# Analog_Transmission.net
KiCad netlist of a schematic drawn in Altium Designer
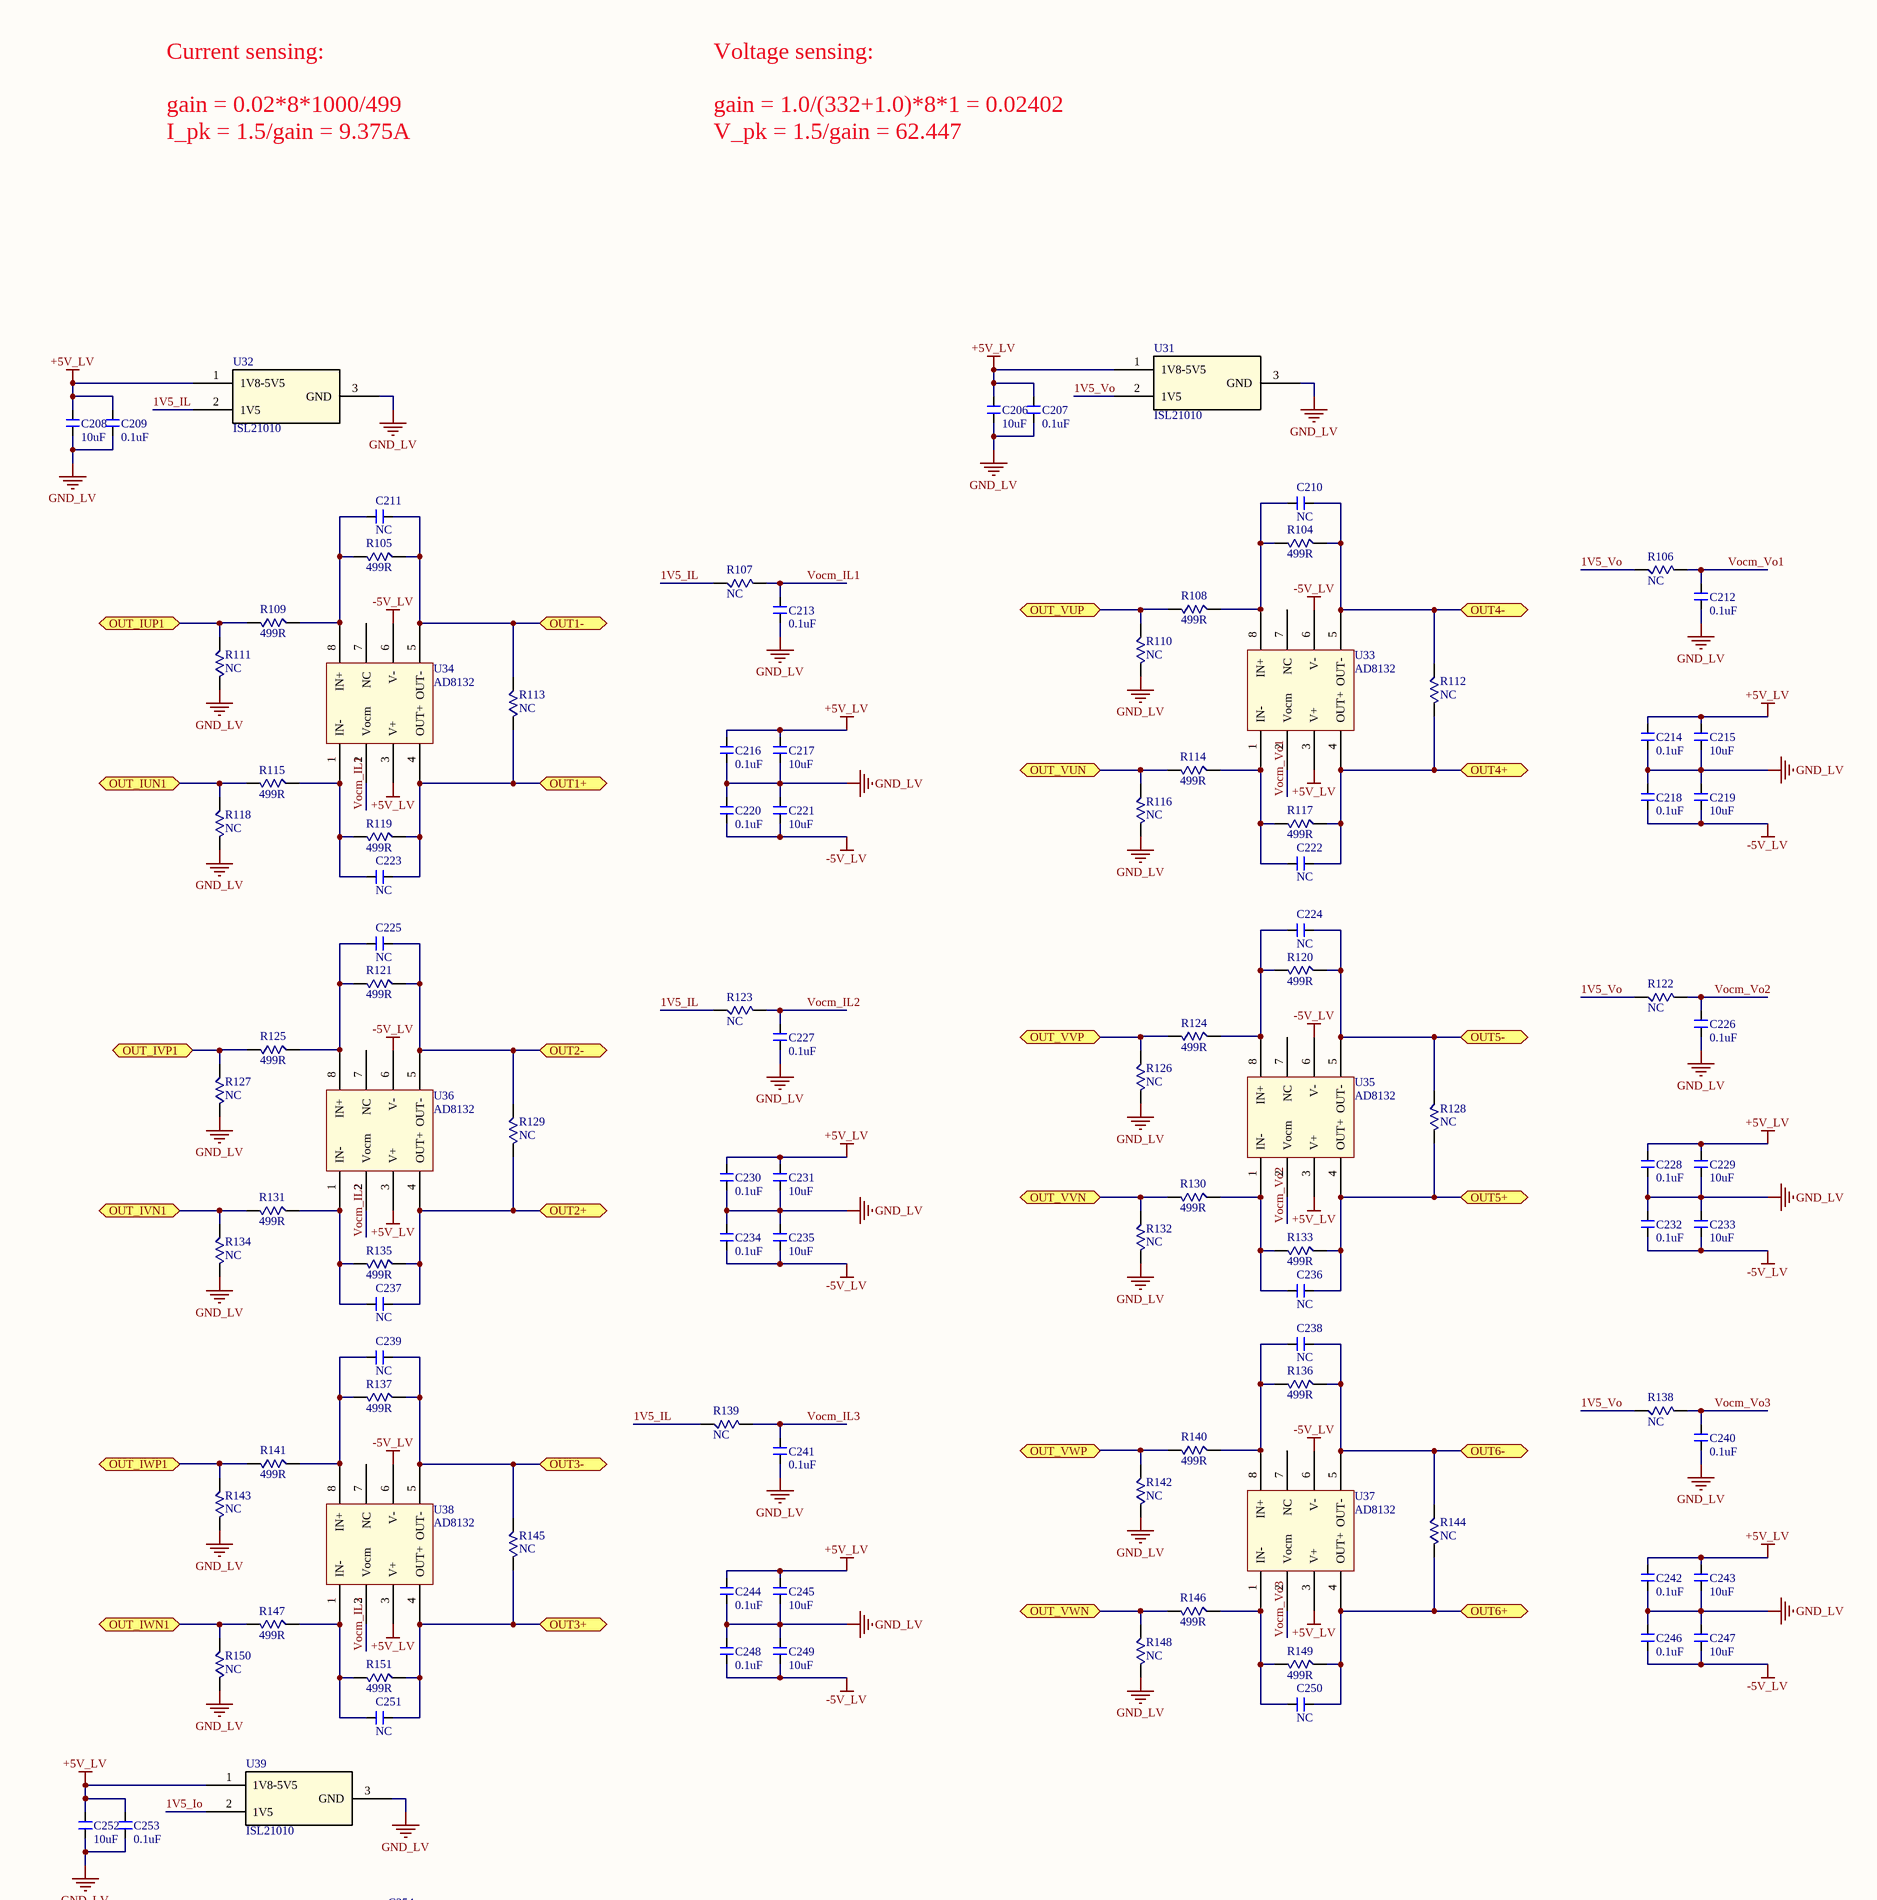
[diagram p0: Analog Transmission.SchDoc, top]
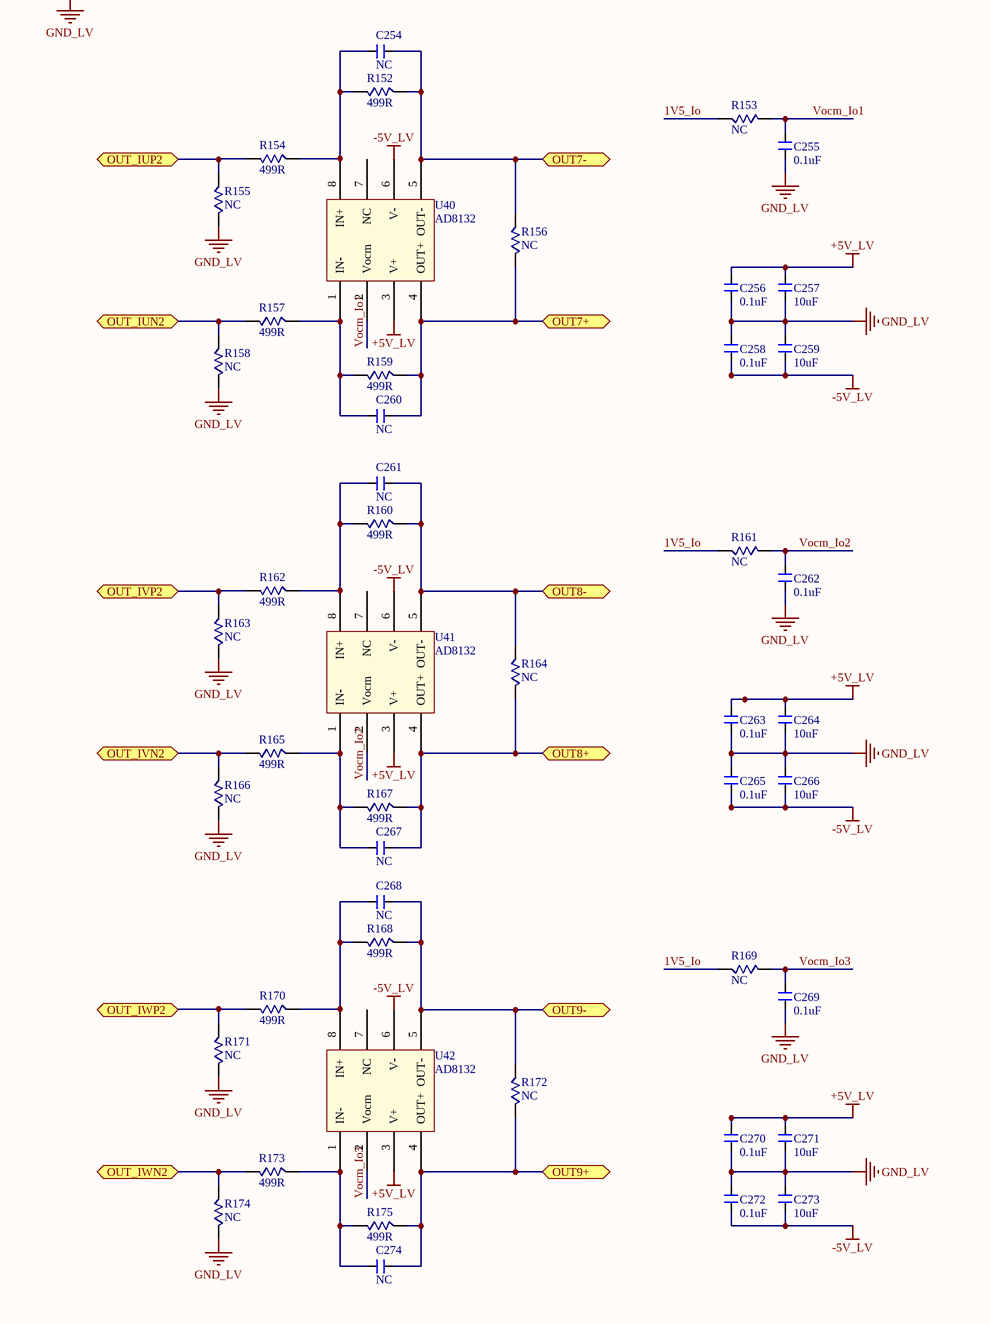
[diagram p1: Analog Transmission.SchDoc, bottom]

(export (version "E")
  (design (tool "Eeschema 10.0.6"))
  (components
    (comp (ref "C206")
      (value "10uF")
      (footprint "0603 (1608 Metric)")
      (description "CAP CER 10UF 35V X5R 0805")
      (fields (field (name "PART") "490-10515-1-ND") (field (name "Comment") "Cap 0603_new"))
      (libsource (lib "Library_Microgrid") (part "Cap 0603_new"))
    )
    (comp (ref "C207")
      (value "0.1uF")
      (footprint "0603 (1608 Metric)")
      (description "CAP CER 0.1UF 50V Y5V 0603")
      (fields (field (name "PART") "311-1343-6-ND") (field (name "Comment") "Cap 0603_new"))
      (libsource (lib "Library_Microgrid") (part "Cap 0603_new"))
    )
    (comp (ref "C208")
      (value "10uF")
      (footprint "0603 (1608 Metric)")
      (description "CAP CER 10UF 35V X5R 0805")
      (fields (field (name "PART") "490-10515-1-ND") (field (name "Comment") "Cap 0603_new"))
      (libsource (lib "Library_Microgrid") (part "Cap 0603_new"))
    )
    (comp (ref "C209")
      (value "0.1uF")
      (footprint "0603 (1608 Metric)")
      (description "CAP CER 0.1UF 50V Y5V 0603")
      (fields (field (name "PART") "311-1343-6-ND") (field (name "Comment") "Cap 0603_new"))
      (libsource (lib "Library_Microgrid") (part "Cap 0603_new"))
    )
    (comp (ref "C210")
      (value "NC")
      (footprint "0603 (1608 Metric)")
      (fields (field (name "Comment") "Cap 0603_new"))
      (libsource (lib "Library_Microgrid") (part "Cap 0603_new"))
    )
    (comp (ref "C211")
      (value "NC")
      (footprint "0603 (1608 Metric)")
      (fields (field (name "Comment") "Cap 0603_new"))
      (libsource (lib "Library_Microgrid") (part "Cap 0603_new"))
    )
    (comp (ref "C212")
      (value "0.1uF")
      (footprint "0603 (1608 Metric)")
      (description "CAP CER 0.1UF 50V Y5V 0603")
      (fields (field (name "PART") "311-1343-6-ND") (field (name "Comment") "Cap 0603_new"))
      (libsource (lib "Library_Microgrid") (part "Cap 0603_new"))
    )
    (comp (ref "C213")
      (value "0.1uF")
      (footprint "0603 (1608 Metric)")
      (description "CAP CER 0.1UF 50V Y5V 0603")
      (fields (field (name "PART") "311-1343-6-ND") (field (name "Comment") "Cap 0603_new"))
      (libsource (lib "Library_Microgrid") (part "Cap 0603_new"))
    )
    (comp (ref "C214")
      (value "0.1uF")
      (footprint "0603 (1608 Metric)")
      (description "CAP CER 0.1UF 50V Y5V 0603")
      (fields (field (name "PART") "311-1343-6-ND") (field (name "Comment") "Cap 0603_new"))
      (libsource (lib "Library_Microgrid") (part "Cap 0603_new"))
    )
    (comp (ref "C215")
      (value "10uF")
      (footprint "0603 (1608 Metric)")
      (description "CAP CER 10UF 35V X5R 0805")
      (fields (field (name "PART") "490-10515-1-ND") (field (name "Comment") "Cap 0603_new"))
      (libsource (lib "Library_Microgrid") (part "Cap 0603_new"))
    )
    (comp (ref "C216")
      (value "0.1uF")
      (footprint "0603 (1608 Metric)")
      (description "CAP CER 0.1UF 50V Y5V 0603")
      (fields (field (name "PART") "311-1343-6-ND") (field (name "Comment") "Cap 0603_new"))
      (libsource (lib "Library_Microgrid") (part "Cap 0603_new"))
    )
    (comp (ref "C217")
      (value "10uF")
      (footprint "0603 (1608 Metric)")
      (description "CAP CER 10UF 35V X5R 0805")
      (fields (field (name "PART") "490-10515-1-ND") (field (name "Comment") "Cap 0603_new"))
      (libsource (lib "Library_Microgrid") (part "Cap 0603_new"))
    )
    (comp (ref "C218")
      (value "0.1uF")
      (footprint "0603 (1608 Metric)")
      (description "CAP CER 0.1UF 50V Y5V 0603")
      (fields (field (name "PART") "311-1343-6-ND") (field (name "Comment") "Cap 0603_new"))
      (libsource (lib "Library_Microgrid") (part "Cap 0603_new"))
    )
    (comp (ref "C219")
      (value "10uF")
      (footprint "0603 (1608 Metric)")
      (description "CAP CER 10UF 35V X5R 0805")
      (fields (field (name "PART") "490-10515-1-ND") (field (name "Comment") "Cap 0603_new"))
      (libsource (lib "Library_Microgrid") (part "Cap 0603_new"))
    )
    (comp (ref "C220")
      (value "0.1uF")
      (footprint "0603 (1608 Metric)")
      (description "CAP CER 0.1UF 50V Y5V 0603")
      (fields (field (name "PART") "311-1343-6-ND") (field (name "Comment") "Cap 0603_new"))
      (libsource (lib "Library_Microgrid") (part "Cap 0603_new"))
    )
    (comp (ref "C221")
      (value "10uF")
      (footprint "0603 (1608 Metric)")
      (description "CAP CER 10UF 35V X5R 0805")
      (fields (field (name "PART") "490-10515-1-ND") (field (name "Comment") "Cap 0603_new"))
      (libsource (lib "Library_Microgrid") (part "Cap 0603_new"))
    )
    (comp (ref "C222")
      (value "NC")
      (footprint "0603 (1608 Metric)")
      (fields (field (name "Comment") "Cap 0603_new"))
      (libsource (lib "Library_Microgrid") (part "Cap 0603_new"))
    )
    (comp (ref "C223")
      (value "NC")
      (footprint "0603 (1608 Metric)")
      (fields (field (name "Comment") "Cap 0603_new"))
      (libsource (lib "Library_Microgrid") (part "Cap 0603_new"))
    )
    (comp (ref "C224")
      (value "NC")
      (footprint "0603 (1608 Metric)")
      (fields (field (name "Comment") "Cap 0603_new"))
      (libsource (lib "Library_Microgrid") (part "Cap 0603_new"))
    )
    (comp (ref "C225")
      (value "NC")
      (footprint "0603 (1608 Metric)")
      (fields (field (name "Comment") "Cap 0603_new"))
      (libsource (lib "Library_Microgrid") (part "Cap 0603_new"))
    )
    (comp (ref "C226")
      (value "0.1uF")
      (footprint "0603 (1608 Metric)")
      (description "CAP CER 0.1UF 50V Y5V 0603")
      (fields (field (name "PART") "311-1343-6-ND") (field (name "Comment") "Cap 0603_new"))
      (libsource (lib "Library_Microgrid") (part "Cap 0603_new"))
    )
    (comp (ref "C227")
      (value "0.1uF")
      (footprint "0603 (1608 Metric)")
      (description "CAP CER 0.1UF 50V Y5V 0603")
      (fields (field (name "PART") "311-1343-6-ND") (field (name "Comment") "Cap 0603_new"))
      (libsource (lib "Library_Microgrid") (part "Cap 0603_new"))
    )
    (comp (ref "C228")
      (value "0.1uF")
      (footprint "0603 (1608 Metric)")
      (description "CAP CER 0.1UF 50V Y5V 0603")
      (fields (field (name "PART") "311-1343-6-ND") (field (name "Comment") "Cap 0603_new"))
      (libsource (lib "Library_Microgrid") (part "Cap 0603_new"))
    )
    (comp (ref "C229")
      (value "10uF")
      (footprint "0603 (1608 Metric)")
      (description "CAP CER 10UF 35V X5R 0805")
      (fields (field (name "PART") "490-10515-1-ND") (field (name "Comment") "Cap 0603_new"))
      (libsource (lib "Library_Microgrid") (part "Cap 0603_new"))
    )
    (comp (ref "C230")
      (value "0.1uF")
      (footprint "0603 (1608 Metric)")
      (description "CAP CER 0.1UF 50V Y5V 0603")
      (fields (field (name "PART") "311-1343-6-ND") (field (name "Comment") "Cap 0603_new"))
      (libsource (lib "Library_Microgrid") (part "Cap 0603_new"))
    )
    (comp (ref "C231")
      (value "10uF")
      (footprint "0603 (1608 Metric)")
      (description "CAP CER 10UF 35V X5R 0805")
      (fields (field (name "PART") "490-10515-1-ND") (field (name "Comment") "Cap 0603_new"))
      (libsource (lib "Library_Microgrid") (part "Cap 0603_new"))
    )
    (comp (ref "C232")
      (value "0.1uF")
      (footprint "0603 (1608 Metric)")
      (description "CAP CER 0.1UF 50V Y5V 0603")
      (fields (field (name "PART") "311-1343-6-ND") (field (name "Comment") "Cap 0603_new"))
      (libsource (lib "Library_Microgrid") (part "Cap 0603_new"))
    )
    (comp (ref "C233")
      (value "10uF")
      (footprint "0603 (1608 Metric)")
      (description "CAP CER 10UF 35V X5R 0805")
      (fields (field (name "PART") "490-10515-1-ND") (field (name "Comment") "Cap 0603_new"))
      (libsource (lib "Library_Microgrid") (part "Cap 0603_new"))
    )
    (comp (ref "C234")
      (value "0.1uF")
      (footprint "0603 (1608 Metric)")
      (description "CAP CER 0.1UF 50V Y5V 0603")
      (fields (field (name "PART") "311-1343-6-ND") (field (name "Comment") "Cap 0603_new"))
      (libsource (lib "Library_Microgrid") (part "Cap 0603_new"))
    )
    (comp (ref "C235")
      (value "10uF")
      (footprint "0603 (1608 Metric)")
      (description "CAP CER 10UF 35V X5R 0805")
      (fields (field (name "PART") "490-10515-1-ND") (field (name "Comment") "Cap 0603_new"))
      (libsource (lib "Library_Microgrid") (part "Cap 0603_new"))
    )
    (comp (ref "C236")
      (value "NC")
      (footprint "0603 (1608 Metric)")
      (fields (field (name "Comment") "Cap 0603_new"))
      (libsource (lib "Library_Microgrid") (part "Cap 0603_new"))
    )
    (comp (ref "C237")
      (value "NC")
      (footprint "0603 (1608 Metric)")
      (fields (field (name "Comment") "Cap 0603_new"))
      (libsource (lib "Library_Microgrid") (part "Cap 0603_new"))
    )
    (comp (ref "C238")
      (value "NC")
      (footprint "0603 (1608 Metric)")
      (fields (field (name "Comment") "Cap 0603_new"))
      (libsource (lib "Library_Microgrid") (part "Cap 0603_new"))
    )
    (comp (ref "C239")
      (value "NC")
      (footprint "0603 (1608 Metric)")
      (fields (field (name "Comment") "Cap 0603_new"))
      (libsource (lib "Library_Microgrid") (part "Cap 0603_new"))
    )
    (comp (ref "C240")
      (value "0.1uF")
      (footprint "0603 (1608 Metric)")
      (description "CAP CER 0.1UF 50V Y5V 0603")
      (fields (field (name "PART") "311-1343-6-ND") (field (name "Comment") "Cap 0603_new"))
      (libsource (lib "Library_Microgrid") (part "Cap 0603_new"))
    )
    (comp (ref "C241")
      (value "0.1uF")
      (footprint "0603 (1608 Metric)")
      (description "CAP CER 0.1UF 50V Y5V 0603")
      (fields (field (name "PART") "311-1343-6-ND") (field (name "Comment") "Cap 0603_new"))
      (libsource (lib "Library_Microgrid") (part "Cap 0603_new"))
    )
    (comp (ref "C242")
      (value "0.1uF")
      (footprint "0603 (1608 Metric)")
      (description "CAP CER 0.1UF 50V Y5V 0603")
      (fields (field (name "PART") "311-1343-6-ND") (field (name "Comment") "Cap 0603_new"))
      (libsource (lib "Library_Microgrid") (part "Cap 0603_new"))
    )
    (comp (ref "C243")
      (value "10uF")
      (footprint "0603 (1608 Metric)")
      (description "CAP CER 10UF 35V X5R 0805")
      (fields (field (name "PART") "490-10515-1-ND") (field (name "Comment") "Cap 0603_new"))
      (libsource (lib "Library_Microgrid") (part "Cap 0603_new"))
    )
    (comp (ref "C244")
      (value "0.1uF")
      (footprint "0603 (1608 Metric)")
      (description "CAP CER 0.1UF 50V Y5V 0603")
      (fields (field (name "PART") "311-1343-6-ND") (field (name "Comment") "Cap 0603_new"))
      (libsource (lib "Library_Microgrid") (part "Cap 0603_new"))
    )
    (comp (ref "C245")
      (value "10uF")
      (footprint "0603 (1608 Metric)")
      (description "CAP CER 10UF 35V X5R 0805")
      (fields (field (name "PART") "490-10515-1-ND") (field (name "Comment") "Cap 0603_new"))
      (libsource (lib "Library_Microgrid") (part "Cap 0603_new"))
    )
    (comp (ref "C246")
      (value "0.1uF")
      (footprint "0603 (1608 Metric)")
      (description "CAP CER 0.1UF 50V Y5V 0603")
      (fields (field (name "PART") "311-1343-6-ND") (field (name "Comment") "Cap 0603_new"))
      (libsource (lib "Library_Microgrid") (part "Cap 0603_new"))
    )
    (comp (ref "C247")
      (value "10uF")
      (footprint "0603 (1608 Metric)")
      (description "CAP CER 10UF 35V X5R 0805")
      (fields (field (name "PART") "490-10515-1-ND") (field (name "Comment") "Cap 0603_new"))
      (libsource (lib "Library_Microgrid") (part "Cap 0603_new"))
    )
    (comp (ref "C248")
      (value "0.1uF")
      (footprint "0603 (1608 Metric)")
      (description "CAP CER 0.1UF 50V Y5V 0603")
      (fields (field (name "PART") "311-1343-6-ND") (field (name "Comment") "Cap 0603_new"))
      (libsource (lib "Library_Microgrid") (part "Cap 0603_new"))
    )
    (comp (ref "C249")
      (value "10uF")
      (footprint "0603 (1608 Metric)")
      (description "CAP CER 10UF 35V X5R 0805")
      (fields (field (name "PART") "490-10515-1-ND") (field (name "Comment") "Cap 0603_new"))
      (libsource (lib "Library_Microgrid") (part "Cap 0603_new"))
    )
    (comp (ref "C250")
      (value "NC")
      (footprint "0603 (1608 Metric)")
      (fields (field (name "Comment") "Cap 0603_new"))
      (libsource (lib "Library_Microgrid") (part "Cap 0603_new"))
    )
    (comp (ref "C251")
      (value "NC")
      (footprint "0603 (1608 Metric)")
      (fields (field (name "Comment") "Cap 0603_new"))
      (libsource (lib "Library_Microgrid") (part "Cap 0603_new"))
    )
    (comp (ref "C252")
      (value "10uF")
      (footprint "0603 (1608 Metric)")
      (description "CAP CER 10UF 35V X5R 0805")
      (fields (field (name "PART") "490-10515-1-ND") (field (name "Comment") "Cap 0603_new"))
      (libsource (lib "Library_Microgrid") (part "Cap 0603_new"))
    )
    (comp (ref "C253")
      (value "0.1uF")
      (footprint "0603 (1608 Metric)")
      (description "CAP CER 0.1UF 50V Y5V 0603")
      (fields (field (name "PART") "311-1343-6-ND") (field (name "Comment") "Cap 0603_new"))
      (libsource (lib "Library_Microgrid") (part "Cap 0603_new"))
    )
    (comp (ref "C254")
      (value "NC")
      (footprint "0603 (1608 Metric)")
      (fields (field (name "Comment") "Cap 0603_new"))
      (libsource (lib "Library_Microgrid") (part "Cap 0603_new"))
    )
    (comp (ref "C255")
      (value "0.1uF")
      (footprint "0603 (1608 Metric)")
      (description "CAP CER 0.1UF 50V Y5V 0603")
      (fields (field (name "PART") "311-1343-6-ND") (field (name "Comment") "Cap 0603_new"))
      (libsource (lib "Library_Microgrid") (part "Cap 0603_new"))
    )
    (comp (ref "C256")
      (value "0.1uF")
      (footprint "0603 (1608 Metric)")
      (description "CAP CER 0.1UF 50V Y5V 0603")
      (fields (field (name "PART") "311-1343-6-ND") (field (name "Comment") "Cap 0603_new"))
      (libsource (lib "Library_Microgrid") (part "Cap 0603_new"))
    )
    (comp (ref "C257")
      (value "10uF")
      (footprint "0603 (1608 Metric)")
      (description "CAP CER 10UF 35V X5R 0805")
      (fields (field (name "PART") "490-10515-1-ND") (field (name "Comment") "Cap 0603_new"))
      (libsource (lib "Library_Microgrid") (part "Cap 0603_new"))
    )
    (comp (ref "C258")
      (value "0.1uF")
      (footprint "0603 (1608 Metric)")
      (description "CAP CER 0.1UF 50V Y5V 0603")
      (fields (field (name "PART") "311-1343-6-ND") (field (name "Comment") "Cap 0603_new"))
      (libsource (lib "Library_Microgrid") (part "Cap 0603_new"))
    )
    (comp (ref "C259")
      (value "10uF")
      (footprint "0603 (1608 Metric)")
      (description "CAP CER 10UF 35V X5R 0805")
      (fields (field (name "PART") "490-10515-1-ND") (field (name "Comment") "Cap 0603_new"))
      (libsource (lib "Library_Microgrid") (part "Cap 0603_new"))
    )
    (comp (ref "C260")
      (value "NC")
      (footprint "0603 (1608 Metric)")
      (fields (field (name "Comment") "Cap 0603_new"))
      (libsource (lib "Library_Microgrid") (part "Cap 0603_new"))
    )
    (comp (ref "C261")
      (value "NC")
      (footprint "0603 (1608 Metric)")
      (fields (field (name "Comment") "Cap 0603_new"))
      (libsource (lib "Library_Microgrid") (part "Cap 0603_new"))
    )
    (comp (ref "C262")
      (value "0.1uF")
      (footprint "0603 (1608 Metric)")
      (description "CAP CER 0.1UF 50V Y5V 0603")
      (fields (field (name "PART") "311-1343-6-ND") (field (name "Comment") "Cap 0603_new"))
      (libsource (lib "Library_Microgrid") (part "Cap 0603_new"))
    )
    (comp (ref "C263")
      (value "0.1uF")
      (footprint "0603 (1608 Metric)")
      (description "CAP CER 0.1UF 50V Y5V 0603")
      (fields (field (name "PART") "311-1343-6-ND") (field (name "Comment") "Cap 0603_new"))
      (libsource (lib "Library_Microgrid") (part "Cap 0603_new"))
    )
    (comp (ref "C264")
      (value "10uF")
      (footprint "0603 (1608 Metric)")
      (description "CAP CER 10UF 35V X5R 0805")
      (fields (field (name "PART") "490-10515-1-ND") (field (name "Comment") "Cap 0603_new"))
      (libsource (lib "Library_Microgrid") (part "Cap 0603_new"))
    )
    (comp (ref "C265")
      (value "0.1uF")
      (footprint "0603 (1608 Metric)")
      (description "CAP CER 0.1UF 50V Y5V 0603")
      (fields (field (name "PART") "311-1343-6-ND") (field (name "Comment") "Cap 0603_new"))
      (libsource (lib "Library_Microgrid") (part "Cap 0603_new"))
    )
    (comp (ref "C266")
      (value "10uF")
      (footprint "0603 (1608 Metric)")
      (description "CAP CER 10UF 35V X5R 0805")
      (fields (field (name "PART") "490-10515-1-ND") (field (name "Comment") "Cap 0603_new"))
      (libsource (lib "Library_Microgrid") (part "Cap 0603_new"))
    )
    (comp (ref "C267")
      (value "NC")
      (footprint "0603 (1608 Metric)")
      (fields (field (name "Comment") "Cap 0603_new"))
      (libsource (lib "Library_Microgrid") (part "Cap 0603_new"))
    )
    (comp (ref "C268")
      (value "NC")
      (footprint "0603 (1608 Metric)")
      (fields (field (name "Comment") "Cap 0603_new"))
      (libsource (lib "Library_Microgrid") (part "Cap 0603_new"))
    )
    (comp (ref "C269")
      (value "0.1uF")
      (footprint "0603 (1608 Metric)")
      (description "CAP CER 0.1UF 50V Y5V 0603")
      (fields (field (name "PART") "311-1343-6-ND") (field (name "Comment") "Cap 0603_new"))
      (libsource (lib "Library_Microgrid") (part "Cap 0603_new"))
    )
    (comp (ref "C270")
      (value "0.1uF")
      (footprint "0603 (1608 Metric)")
      (description "CAP CER 0.1UF 50V Y5V 0603")
      (fields (field (name "PART") "311-1343-6-ND") (field (name "Comment") "Cap 0603_new"))
      (libsource (lib "Library_Microgrid") (part "Cap 0603_new"))
    )
    (comp (ref "C271")
      (value "10uF")
      (footprint "0603 (1608 Metric)")
      (description "CAP CER 10UF 35V X5R 0805")
      (fields (field (name "PART") "490-10515-1-ND") (field (name "Comment") "Cap 0603_new"))
      (libsource (lib "Library_Microgrid") (part "Cap 0603_new"))
    )
    (comp (ref "C272")
      (value "0.1uF")
      (footprint "0603 (1608 Metric)")
      (description "CAP CER 0.1UF 50V Y5V 0603")
      (fields (field (name "PART") "311-1343-6-ND") (field (name "Comment") "Cap 0603_new"))
      (libsource (lib "Library_Microgrid") (part "Cap 0603_new"))
    )
    (comp (ref "C273")
      (value "10uF")
      (footprint "0603 (1608 Metric)")
      (description "CAP CER 10UF 35V X5R 0805")
      (fields (field (name "PART") "490-10515-1-ND") (field (name "Comment") "Cap 0603_new"))
      (libsource (lib "Library_Microgrid") (part "Cap 0603_new"))
    )
    (comp (ref "C274")
      (value "NC")
      (footprint "0603 (1608 Metric)")
      (fields (field (name "Comment") "Cap 0603_new"))
      (libsource (lib "Library_Microgrid") (part "Cap 0603_new"))
    )
    (comp (ref "R104")
      (value "499R")
      (footprint "0603 (1608 Metric)")
      (description "RES SMD 499 OHM 0.1% 1/10W 0603")
      (fields (field (name "PART") "RG16P499BCT-ND") (field (name "Comment") "Resistor 0603"))
      (libsource (lib "Library_Microgrid") (part "Resistor 0603"))
    )
    (comp (ref "R105")
      (value "499R")
      (footprint "0603 (1608 Metric)")
      (description "RES SMD 499 OHM 0.1% 1/10W 0603")
      (fields (field (name "PART") "RG16P499BCT-ND") (field (name "Comment") "Resistor 0603"))
      (libsource (lib "Library_Microgrid") (part "Resistor 0603"))
    )
    (comp (ref "R106")
      (value "NC")
      (footprint "0603 (1608 Metric)")
      (fields (field (name "Comment") "Resistor 0603"))
      (libsource (lib "Library_Microgrid") (part "Resistor 0603"))
    )
    (comp (ref "R107")
      (value "NC")
      (footprint "0603 (1608 Metric)")
      (fields (field (name "Comment") "Resistor 0603"))
      (libsource (lib "Library_Microgrid") (part "Resistor 0603"))
    )
    (comp (ref "R108")
      (value "499R")
      (footprint "0603 (1608 Metric)")
      (description "RES SMD 499 OHM 0.1% 1/10W 0603")
      (fields (field (name "PART") "RG16P499BCT-ND") (field (name "Comment") "Resistor 0603"))
      (libsource (lib "Library_Microgrid") (part "Resistor 0603"))
    )
    (comp (ref "R109")
      (value "499R")
      (footprint "0603 (1608 Metric)")
      (description "RES SMD 499 OHM 0.1% 1/10W 0603")
      (fields (field (name "PART") "RG16P499BCT-ND") (field (name "Comment") "Resistor 0603"))
      (libsource (lib "Library_Microgrid") (part "Resistor 0603"))
    )
    (comp (ref "R110")
      (value "NC")
      (footprint "0603 (1608 Metric)")
      (fields (field (name "Comment") "Resistor 0603"))
      (libsource (lib "Library_Microgrid") (part "Resistor 0603"))
    )
    (comp (ref "R111")
      (value "NC")
      (footprint "0603 (1608 Metric)")
      (fields (field (name "Comment") "Resistor 0603"))
      (libsource (lib "Library_Microgrid") (part "Resistor 0603"))
    )
    (comp (ref "R112")
      (value "NC")
      (footprint "0603 (1608 Metric)")
      (fields (field (name "Comment") "Resistor 0603"))
      (libsource (lib "Library_Microgrid") (part "Resistor 0603"))
    )
    (comp (ref "R113")
      (value "NC")
      (footprint "0603 (1608 Metric)")
      (fields (field (name "Comment") "Resistor 0603"))
      (libsource (lib "Library_Microgrid") (part "Resistor 0603"))
    )
    (comp (ref "R114")
      (value "499R")
      (footprint "0603 (1608 Metric)")
      (description "RES SMD 499 OHM 0.1% 1/10W 0603")
      (fields (field (name "PART") "RG16P499BCT-ND") (field (name "Comment") "Resistor 0603"))
      (libsource (lib "Library_Microgrid") (part "Resistor 0603"))
    )
    (comp (ref "R115")
      (value "499R")
      (footprint "0603 (1608 Metric)")
      (description "RES SMD 499 OHM 0.1% 1/10W 0603")
      (fields (field (name "PART") "RG16P499BCT-ND") (field (name "Comment") "Resistor 0603"))
      (libsource (lib "Library_Microgrid") (part "Resistor 0603"))
    )
    (comp (ref "R116")
      (value "NC")
      (footprint "0603 (1608 Metric)")
      (fields (field (name "Comment") "Resistor 0603"))
      (libsource (lib "Library_Microgrid") (part "Resistor 0603"))
    )
    (comp (ref "R117")
      (value "499R")
      (footprint "0603 (1608 Metric)")
      (description "RES SMD 499 OHM 0.1% 1/10W 0603")
      (fields (field (name "PART") "RG16P499BCT-ND") (field (name "Comment") "Resistor 0603"))
      (libsource (lib "Library_Microgrid") (part "Resistor 0603"))
    )
    (comp (ref "R118")
      (value "NC")
      (footprint "0603 (1608 Metric)")
      (fields (field (name "Comment") "Resistor 0603"))
      (libsource (lib "Library_Microgrid") (part "Resistor 0603"))
    )
    (comp (ref "R119")
      (value "499R")
      (footprint "0603 (1608 Metric)")
      (description "RES SMD 499 OHM 0.1% 1/10W 0603")
      (fields (field (name "PART") "RG16P499BCT-ND") (field (name "Comment") "Resistor 0603"))
      (libsource (lib "Library_Microgrid") (part "Resistor 0603"))
    )
    (comp (ref "R120")
      (value "499R")
      (footprint "0603 (1608 Metric)")
      (description "RES SMD 499 OHM 0.1% 1/10W 0603")
      (fields (field (name "PART") "RG16P499BCT-ND") (field (name "Comment") "Resistor 0603"))
      (libsource (lib "Library_Microgrid") (part "Resistor 0603"))
    )
    (comp (ref "R121")
      (value "499R")
      (footprint "0603 (1608 Metric)")
      (description "RES SMD 499 OHM 0.1% 1/10W 0603")
      (fields (field (name "PART") "RG16P499BCT-ND") (field (name "Comment") "Resistor 0603"))
      (libsource (lib "Library_Microgrid") (part "Resistor 0603"))
    )
    (comp (ref "R122")
      (value "NC")
      (footprint "0603 (1608 Metric)")
      (fields (field (name "Comment") "Resistor 0603"))
      (libsource (lib "Library_Microgrid") (part "Resistor 0603"))
    )
    (comp (ref "R123")
      (value "NC")
      (footprint "0603 (1608 Metric)")
      (fields (field (name "Comment") "Resistor 0603"))
      (libsource (lib "Library_Microgrid") (part "Resistor 0603"))
    )
    (comp (ref "R124")
      (value "499R")
      (footprint "0603 (1608 Metric)")
      (description "RES SMD 499 OHM 0.1% 1/10W 0603")
      (fields (field (name "PART") "RG16P499BCT-ND") (field (name "Comment") "Resistor 0603"))
      (libsource (lib "Library_Microgrid") (part "Resistor 0603"))
    )
    (comp (ref "R125")
      (value "499R")
      (footprint "0603 (1608 Metric)")
      (description "RES SMD 499 OHM 0.1% 1/10W 0603")
      (fields (field (name "PART") "RG16P499BCT-ND") (field (name "Comment") "Resistor 0603"))
      (libsource (lib "Library_Microgrid") (part "Resistor 0603"))
    )
    (comp (ref "R126")
      (value "NC")
      (footprint "0603 (1608 Metric)")
      (fields (field (name "Comment") "Resistor 0603"))
      (libsource (lib "Library_Microgrid") (part "Resistor 0603"))
    )
    (comp (ref "R127")
      (value "NC")
      (footprint "0603 (1608 Metric)")
      (fields (field (name "Comment") "Resistor 0603"))
      (libsource (lib "Library_Microgrid") (part "Resistor 0603"))
    )
    (comp (ref "R128")
      (value "NC")
      (footprint "0603 (1608 Metric)")
      (fields (field (name "Comment") "Resistor 0603"))
      (libsource (lib "Library_Microgrid") (part "Resistor 0603"))
    )
    (comp (ref "R129")
      (value "NC")
      (footprint "0603 (1608 Metric)")
      (fields (field (name "Comment") "Resistor 0603"))
      (libsource (lib "Library_Microgrid") (part "Resistor 0603"))
    )
    (comp (ref "R130")
      (value "499R")
      (footprint "0603 (1608 Metric)")
      (description "RES SMD 499 OHM 0.1% 1/10W 0603")
      (fields (field (name "PART") "RG16P499BCT-ND") (field (name "Comment") "Resistor 0603"))
      (libsource (lib "Library_Microgrid") (part "Resistor 0603"))
    )
    (comp (ref "R131")
      (value "499R")
      (footprint "0603 (1608 Metric)")
      (description "RES SMD 499 OHM 0.1% 1/10W 0603")
      (fields (field (name "PART") "RG16P499BCT-ND") (field (name "Comment") "Resistor 0603"))
      (libsource (lib "Library_Microgrid") (part "Resistor 0603"))
    )
    (comp (ref "R132")
      (value "NC")
      (footprint "0603 (1608 Metric)")
      (fields (field (name "Comment") "Resistor 0603"))
      (libsource (lib "Library_Microgrid") (part "Resistor 0603"))
    )
    (comp (ref "R133")
      (value "499R")
      (footprint "0603 (1608 Metric)")
      (description "RES SMD 499 OHM 0.1% 1/10W 0603")
      (fields (field (name "PART") "RG16P499BCT-ND") (field (name "Comment") "Resistor 0603"))
      (libsource (lib "Library_Microgrid") (part "Resistor 0603"))
    )
    (comp (ref "R134")
      (value "NC")
      (footprint "0603 (1608 Metric)")
      (fields (field (name "Comment") "Resistor 0603"))
      (libsource (lib "Library_Microgrid") (part "Resistor 0603"))
    )
    (comp (ref "R135")
      (value "499R")
      (footprint "0603 (1608 Metric)")
      (description "RES SMD 499 OHM 0.1% 1/10W 0603")
      (fields (field (name "PART") "RG16P499BCT-ND") (field (name "Comment") "Resistor 0603"))
      (libsource (lib "Library_Microgrid") (part "Resistor 0603"))
    )
    (comp (ref "R136")
      (value "499R")
      (footprint "0603 (1608 Metric)")
      (description "RES SMD 499 OHM 0.1% 1/10W 0603")
      (fields (field (name "PART") "RG16P499BCT-ND") (field (name "Comment") "Resistor 0603"))
      (libsource (lib "Library_Microgrid") (part "Resistor 0603"))
    )
    (comp (ref "R137")
      (value "499R")
      (footprint "0603 (1608 Metric)")
      (description "RES SMD 499 OHM 0.1% 1/10W 0603")
      (fields (field (name "PART") "RG16P499BCT-ND") (field (name "Comment") "Resistor 0603"))
      (libsource (lib "Library_Microgrid") (part "Resistor 0603"))
    )
    (comp (ref "R138")
      (value "NC")
      (footprint "0603 (1608 Metric)")
      (fields (field (name "Comment") "Resistor 0603"))
      (libsource (lib "Library_Microgrid") (part "Resistor 0603"))
    )
    (comp (ref "R139")
      (value "NC")
      (footprint "0603 (1608 Metric)")
      (fields (field (name "Comment") "Resistor 0603"))
      (libsource (lib "Library_Microgrid") (part "Resistor 0603"))
    )
    (comp (ref "R140")
      (value "499R")
      (footprint "0603 (1608 Metric)")
      (description "RES SMD 499 OHM 0.1% 1/10W 0603")
      (fields (field (name "PART") "RG16P499BCT-ND") (field (name "Comment") "Resistor 0603"))
      (libsource (lib "Library_Microgrid") (part "Resistor 0603"))
    )
    (comp (ref "R141")
      (value "499R")
      (footprint "0603 (1608 Metric)")
      (description "RES SMD 499 OHM 0.1% 1/10W 0603")
      (fields (field (name "PART") "RG16P499BCT-ND") (field (name "Comment") "Resistor 0603"))
      (libsource (lib "Library_Microgrid") (part "Resistor 0603"))
    )
    (comp (ref "R142")
      (value "NC")
      (footprint "0603 (1608 Metric)")
      (fields (field (name "Comment") "Resistor 0603"))
      (libsource (lib "Library_Microgrid") (part "Resistor 0603"))
    )
    (comp (ref "R143")
      (value "NC")
      (footprint "0603 (1608 Metric)")
      (fields (field (name "Comment") "Resistor 0603"))
      (libsource (lib "Library_Microgrid") (part "Resistor 0603"))
    )
    (comp (ref "R144")
      (value "NC")
      (footprint "0603 (1608 Metric)")
      (fields (field (name "Comment") "Resistor 0603"))
      (libsource (lib "Library_Microgrid") (part "Resistor 0603"))
    )
    (comp (ref "R145")
      (value "NC")
      (footprint "0603 (1608 Metric)")
      (fields (field (name "Comment") "Resistor 0603"))
      (libsource (lib "Library_Microgrid") (part "Resistor 0603"))
    )
    (comp (ref "R146")
      (value "499R")
      (footprint "0603 (1608 Metric)")
      (description "RES SMD 499 OHM 0.1% 1/10W 0603")
      (fields (field (name "PART") "RG16P499BCT-ND") (field (name "Comment") "Resistor 0603"))
      (libsource (lib "Library_Microgrid") (part "Resistor 0603"))
    )
    (comp (ref "R147")
      (value "499R")
      (footprint "0603 (1608 Metric)")
      (description "RES SMD 499 OHM 0.1% 1/10W 0603")
      (fields (field (name "PART") "RG16P499BCT-ND") (field (name "Comment") "Resistor 0603"))
      (libsource (lib "Library_Microgrid") (part "Resistor 0603"))
    )
    (comp (ref "R148")
      (value "NC")
      (footprint "0603 (1608 Metric)")
      (fields (field (name "Comment") "Resistor 0603"))
      (libsource (lib "Library_Microgrid") (part "Resistor 0603"))
    )
    (comp (ref "R149")
      (value "499R")
      (footprint "0603 (1608 Metric)")
      (description "RES SMD 499 OHM 0.1% 1/10W 0603")
      (fields (field (name "PART") "RG16P499BCT-ND") (field (name "Comment") "Resistor 0603"))
      (libsource (lib "Library_Microgrid") (part "Resistor 0603"))
    )
    (comp (ref "R150")
      (value "NC")
      (footprint "0603 (1608 Metric)")
      (fields (field (name "Comment") "Resistor 0603"))
      (libsource (lib "Library_Microgrid") (part "Resistor 0603"))
    )
    (comp (ref "R151")
      (value "499R")
      (footprint "0603 (1608 Metric)")
      (description "RES SMD 499 OHM 0.1% 1/10W 0603")
      (fields (field (name "PART") "RG16P499BCT-ND") (field (name "Comment") "Resistor 0603"))
      (libsource (lib "Library_Microgrid") (part "Resistor 0603"))
    )
    (comp (ref "R152")
      (value "499R")
      (footprint "0603 (1608 Metric)")
      (description "RES SMD 499 OHM 0.1% 1/10W 0603")
      (fields (field (name "PART") "RG16P499BCT-ND") (field (name "Comment") "Resistor 0603"))
      (libsource (lib "Library_Microgrid") (part "Resistor 0603"))
    )
    (comp (ref "R153")
      (value "NC")
      (footprint "0603 (1608 Metric)")
      (fields (field (name "Comment") "Resistor 0603"))
      (libsource (lib "Library_Microgrid") (part "Resistor 0603"))
    )
    (comp (ref "R154")
      (value "499R")
      (footprint "0603 (1608 Metric)")
      (description "RES SMD 499 OHM 0.1% 1/10W 0603")
      (fields (field (name "PART") "RG16P499BCT-ND") (field (name "Comment") "Resistor 0603"))
      (libsource (lib "Library_Microgrid") (part "Resistor 0603"))
    )
    (comp (ref "R155")
      (value "NC")
      (footprint "0603 (1608 Metric)")
      (fields (field (name "Comment") "Resistor 0603"))
      (libsource (lib "Library_Microgrid") (part "Resistor 0603"))
    )
    (comp (ref "R156")
      (value "NC")
      (footprint "0603 (1608 Metric)")
      (fields (field (name "Comment") "Resistor 0603"))
      (libsource (lib "Library_Microgrid") (part "Resistor 0603"))
    )
    (comp (ref "R157")
      (value "499R")
      (footprint "0603 (1608 Metric)")
      (description "RES SMD 499 OHM 0.1% 1/10W 0603")
      (fields (field (name "PART") "RG16P499BCT-ND") (field (name "Comment") "Resistor 0603"))
      (libsource (lib "Library_Microgrid") (part "Resistor 0603"))
    )
    (comp (ref "R158")
      (value "NC")
      (footprint "0603 (1608 Metric)")
      (fields (field (name "Comment") "Resistor 0603"))
      (libsource (lib "Library_Microgrid") (part "Resistor 0603"))
    )
    (comp (ref "R159")
      (value "499R")
      (footprint "0603 (1608 Metric)")
      (description "RES SMD 499 OHM 0.1% 1/10W 0603")
      (fields (field (name "PART") "RG16P499BCT-ND") (field (name "Comment") "Resistor 0603"))
      (libsource (lib "Library_Microgrid") (part "Resistor 0603"))
    )
    (comp (ref "R160")
      (value "499R")
      (footprint "0603 (1608 Metric)")
      (description "RES SMD 499 OHM 0.1% 1/10W 0603")
      (fields (field (name "PART") "RG16P499BCT-ND") (field (name "Comment") "Resistor 0603"))
      (libsource (lib "Library_Microgrid") (part "Resistor 0603"))
    )
    (comp (ref "R161")
      (value "NC")
      (footprint "0603 (1608 Metric)")
      (fields (field (name "Comment") "Resistor 0603"))
      (libsource (lib "Library_Microgrid") (part "Resistor 0603"))
    )
    (comp (ref "R162")
      (value "499R")
      (footprint "0603 (1608 Metric)")
      (description "RES SMD 499 OHM 0.1% 1/10W 0603")
      (fields (field (name "PART") "RG16P499BCT-ND") (field (name "Comment") "Resistor 0603"))
      (libsource (lib "Library_Microgrid") (part "Resistor 0603"))
    )
    (comp (ref "R163")
      (value "NC")
      (footprint "0603 (1608 Metric)")
      (fields (field (name "Comment") "Resistor 0603"))
      (libsource (lib "Library_Microgrid") (part "Resistor 0603"))
    )
    (comp (ref "R164")
      (value "NC")
      (footprint "0603 (1608 Metric)")
      (fields (field (name "Comment") "Resistor 0603"))
      (libsource (lib "Library_Microgrid") (part "Resistor 0603"))
    )
    (comp (ref "R165")
      (value "499R")
      (footprint "0603 (1608 Metric)")
      (description "RES SMD 499 OHM 0.1% 1/10W 0603")
      (fields (field (name "PART") "RG16P499BCT-ND") (field (name "Comment") "Resistor 0603"))
      (libsource (lib "Library_Microgrid") (part "Resistor 0603"))
    )
    (comp (ref "R166")
      (value "NC")
      (footprint "0603 (1608 Metric)")
      (fields (field (name "Comment") "Resistor 0603"))
      (libsource (lib "Library_Microgrid") (part "Resistor 0603"))
    )
    (comp (ref "R167")
      (value "499R")
      (footprint "0603 (1608 Metric)")
      (description "RES SMD 499 OHM 0.1% 1/10W 0603")
      (fields (field (name "PART") "RG16P499BCT-ND") (field (name "Comment") "Resistor 0603"))
      (libsource (lib "Library_Microgrid") (part "Resistor 0603"))
    )
    (comp (ref "R168")
      (value "499R")
      (footprint "0603 (1608 Metric)")
      (description "RES SMD 499 OHM 0.1% 1/10W 0603")
      (fields (field (name "PART") "RG16P499BCT-ND") (field (name "Comment") "Resistor 0603"))
      (libsource (lib "Library_Microgrid") (part "Resistor 0603"))
    )
    (comp (ref "R169")
      (value "NC")
      (footprint "0603 (1608 Metric)")
      (fields (field (name "Comment") "Resistor 0603"))
      (libsource (lib "Library_Microgrid") (part "Resistor 0603"))
    )
    (comp (ref "R170")
      (value "499R")
      (footprint "0603 (1608 Metric)")
      (description "RES SMD 499 OHM 0.1% 1/10W 0603")
      (fields (field (name "PART") "RG16P499BCT-ND") (field (name "Comment") "Resistor 0603"))
      (libsource (lib "Library_Microgrid") (part "Resistor 0603"))
    )
    (comp (ref "R171")
      (value "NC")
      (footprint "0603 (1608 Metric)")
      (fields (field (name "Comment") "Resistor 0603"))
      (libsource (lib "Library_Microgrid") (part "Resistor 0603"))
    )
    (comp (ref "R172")
      (value "NC")
      (footprint "0603 (1608 Metric)")
      (fields (field (name "Comment") "Resistor 0603"))
      (libsource (lib "Library_Microgrid") (part "Resistor 0603"))
    )
    (comp (ref "R173")
      (value "499R")
      (footprint "0603 (1608 Metric)")
      (description "RES SMD 499 OHM 0.1% 1/10W 0603")
      (fields (field (name "PART") "RG16P499BCT-ND") (field (name "Comment") "Resistor 0603"))
      (libsource (lib "Library_Microgrid") (part "Resistor 0603"))
    )
    (comp (ref "R174")
      (value "NC")
      (footprint "0603 (1608 Metric)")
      (fields (field (name "Comment") "Resistor 0603"))
      (libsource (lib "Library_Microgrid") (part "Resistor 0603"))
    )
    (comp (ref "R175")
      (value "499R")
      (footprint "0603 (1608 Metric)")
      (description "RES SMD 499 OHM 0.1% 1/10W 0603")
      (fields (field (name "PART") "RG16P499BCT-ND") (field (name "Comment") "Resistor 0603"))
      (libsource (lib "Library_Microgrid") (part "Resistor 0603"))
    )
    (comp (ref "U31")
      (value "ISL21010")
      (footprint "SOT_23")
      (description "Series Voltage Reference IC ±0.2% 25mA SOT-23-3")
      (fields (field (name "PART") "ISL21010CFH315Z-TKCT-ND"))
      (libsource (lib "Library_Microgrid") (part "ISL21010"))
    )
    (comp (ref "U32")
      (value "ISL21010")
      (footprint "SOT_23")
      (description "Series Voltage Reference IC ±0.2% 25mA SOT-23-3")
      (fields (field (name "PART") "ISL21010CFH315Z-TKCT-ND"))
      (libsource (lib "Library_Microgrid") (part "ISL21010"))
    )
    (comp (ref "U33")
      (value "AD8132")
      (footprint "Miscellaneous Devices:SO8_L")
      (description "IC OPAMP DIFF 360MHZ 8MSOP")
      (fields (field (name "PART") "AD8132WARMZ-R7CT-ND"))
      (libsource (lib "Library_Microgrid") (part "AD8132"))
    )
    (comp (ref "U34")
      (value "AD8132")
      (footprint "Miscellaneous Devices:SO8_L")
      (description "IC OPAMP DIFF 360MHZ 8MSOP")
      (fields (field (name "PART") "AD8132WARMZ-R7CT-ND"))
      (libsource (lib "Library_Microgrid") (part "AD8132"))
    )
    (comp (ref "U35")
      (value "AD8132")
      (footprint "Miscellaneous Devices:SO8_L")
      (description "IC OPAMP DIFF 360MHZ 8MSOP")
      (fields (field (name "PART") "AD8132WARMZ-R7CT-ND"))
      (libsource (lib "Library_Microgrid") (part "AD8132"))
    )
    (comp (ref "U36")
      (value "AD8132")
      (footprint "Miscellaneous Devices:SO8_L")
      (description "IC OPAMP DIFF 360MHZ 8MSOP")
      (fields (field (name "PART") "AD8132WARMZ-R7CT-ND"))
      (libsource (lib "Library_Microgrid") (part "AD8132"))
    )
    (comp (ref "U37")
      (value "AD8132")
      (footprint "Miscellaneous Devices:SO8_L")
      (description "IC OPAMP DIFF 360MHZ 8MSOP")
      (fields (field (name "PART") "AD8132WARMZ-R7CT-ND"))
      (libsource (lib "Library_Microgrid") (part "AD8132"))
    )
    (comp (ref "U38")
      (value "AD8132")
      (footprint "Miscellaneous Devices:SO8_L")
      (description "IC OPAMP DIFF 360MHZ 8MSOP")
      (fields (field (name "PART") "AD8132WARMZ-R7CT-ND"))
      (libsource (lib "Library_Microgrid") (part "AD8132"))
    )
    (comp (ref "U39")
      (value "ISL21010")
      (footprint "SOT_23")
      (description "Series Voltage Reference IC ±0.2% 25mA SOT-23-3")
      (fields (field (name "PART") "ISL21010CFH315Z-TKCT-ND"))
      (libsource (lib "Library_Microgrid") (part "ISL21010"))
    )
    (comp (ref "U40")
      (value "AD8132")
      (footprint "Miscellaneous Devices:SO8_L")
      (description "IC OPAMP DIFF 360MHZ 8MSOP")
      (fields (field (name "PART") "AD8132WARMZ-R7CT-ND"))
      (libsource (lib "Library_Microgrid") (part "AD8132"))
    )
    (comp (ref "U41")
      (value "AD8132")
      (footprint "Miscellaneous Devices:SO8_L")
      (description "IC OPAMP DIFF 360MHZ 8MSOP")
      (fields (field (name "PART") "AD8132WARMZ-R7CT-ND"))
      (libsource (lib "Library_Microgrid") (part "AD8132"))
    )
    (comp (ref "U42")
      (value "AD8132")
      (footprint "Miscellaneous Devices:SO8_L")
      (description "IC OPAMP DIFF 360MHZ 8MSOP")
      (fields (field (name "PART") "AD8132WARMZ-R7CT-ND"))
      (libsource (lib "Library_Microgrid") (part "AD8132"))
    )
  )
  (nets
    (net (code "1") (name "+5V_LV") (class "Default")
      (node (ref "C206") (pin "2") (pinfunction "OUT_2") (pintype "passive"))
      (node (ref "C207") (pin "2") (pinfunction "OUT_2") (pintype "passive"))
      (node (ref "C208") (pin "2") (pinfunction "OUT_2") (pintype "passive"))
      (node (ref "C209") (pin "2") (pinfunction "OUT_2") (pintype "passive"))
      (node (ref "C214") (pin "2") (pinfunction "OUT_2") (pintype "passive"))
      (node (ref "C215") (pin "2") (pinfunction "OUT_2") (pintype "passive"))
      (node (ref "C216") (pin "2") (pinfunction "OUT_2") (pintype "passive"))
      (node (ref "C217") (pin "2") (pinfunction "OUT_2") (pintype "passive"))
      (node (ref "C228") (pin "2") (pinfunction "OUT_2") (pintype "passive"))
      (node (ref "C229") (pin "2") (pinfunction "OUT_2") (pintype "passive"))
      (node (ref "C230") (pin "2") (pinfunction "OUT_2") (pintype "passive"))
      (node (ref "C231") (pin "2") (pinfunction "OUT_2") (pintype "passive"))
      (node (ref "C242") (pin "2") (pinfunction "OUT_2") (pintype "passive"))
      (node (ref "C243") (pin "2") (pinfunction "OUT_2") (pintype "passive"))
      (node (ref "C244") (pin "2") (pinfunction "OUT_2") (pintype "passive"))
      (node (ref "C245") (pin "2") (pinfunction "OUT_2") (pintype "passive"))
      (node (ref "C252") (pin "2") (pinfunction "OUT_2") (pintype "passive"))
      (node (ref "C253") (pin "2") (pinfunction "OUT_2") (pintype "passive"))
      (node (ref "C256") (pin "2") (pinfunction "OUT_2") (pintype "passive"))
      (node (ref "C257") (pin "2") (pinfunction "OUT_2") (pintype "passive"))
      (node (ref "C263") (pin "2") (pinfunction "OUT_2") (pintype "passive"))
      (node (ref "C264") (pin "2") (pinfunction "OUT_2") (pintype "passive"))
      (node (ref "C270") (pin "2") (pinfunction "OUT_2") (pintype "passive"))
      (node (ref "C271") (pin "2") (pinfunction "OUT_2") (pintype "passive"))
      (node (ref "U31") (pin "1") (pinfunction "1V8-5V5_1") (pintype "passive"))
      (node (ref "U32") (pin "1") (pinfunction "1V8-5V5_1") (pintype "passive"))
      (node (ref "U33") (pin "3") (pinfunction "V+_3") (pintype "passive"))
      (node (ref "U34") (pin "3") (pinfunction "V+_3") (pintype "passive"))
      (node (ref "U35") (pin "3") (pinfunction "V+_3") (pintype "passive"))
      (node (ref "U36") (pin "3") (pinfunction "V+_3") (pintype "passive"))
      (node (ref "U37") (pin "3") (pinfunction "V+_3") (pintype "passive"))
      (node (ref "U38") (pin "3") (pinfunction "V+_3") (pintype "passive"))
      (node (ref "U39") (pin "1") (pinfunction "1V8-5V5_1") (pintype "passive"))
      (node (ref "U40") (pin "3") (pinfunction "V+_3") (pintype "passive"))
      (node (ref "U41") (pin "3") (pinfunction "V+_3") (pintype "passive"))
      (node (ref "U42") (pin "3") (pinfunction "V+_3") (pintype "passive"))
    )
    (net (code "2") (name "-5V_LV") (class "Default")
      (node (ref "C218") (pin "1") (pinfunction "OUT_1") (pintype "passive"))
      (node (ref "C219") (pin "1") (pinfunction "OUT_1") (pintype "passive"))
      (node (ref "C220") (pin "1") (pinfunction "OUT_1") (pintype "passive"))
      (node (ref "C221") (pin "1") (pinfunction "OUT_1") (pintype "passive"))
      (node (ref "C232") (pin "1") (pinfunction "OUT_1") (pintype "passive"))
      (node (ref "C233") (pin "1") (pinfunction "OUT_1") (pintype "passive"))
      (node (ref "C234") (pin "1") (pinfunction "OUT_1") (pintype "passive"))
      (node (ref "C235") (pin "1") (pinfunction "OUT_1") (pintype "passive"))
      (node (ref "C246") (pin "1") (pinfunction "OUT_1") (pintype "passive"))
      (node (ref "C247") (pin "1") (pinfunction "OUT_1") (pintype "passive"))
      (node (ref "C248") (pin "1") (pinfunction "OUT_1") (pintype "passive"))
      (node (ref "C249") (pin "1") (pinfunction "OUT_1") (pintype "passive"))
      (node (ref "C258") (pin "1") (pinfunction "OUT_1") (pintype "passive"))
      (node (ref "C259") (pin "1") (pinfunction "OUT_1") (pintype "passive"))
      (node (ref "C265") (pin "1") (pinfunction "OUT_1") (pintype "passive"))
      (node (ref "C266") (pin "1") (pinfunction "OUT_1") (pintype "passive"))
      (node (ref "C272") (pin "1") (pinfunction "OUT_1") (pintype "passive"))
      (node (ref "C273") (pin "1") (pinfunction "OUT_1") (pintype "passive"))
      (node (ref "U33") (pin "6") (pinfunction "V-_6") (pintype "passive"))
      (node (ref "U34") (pin "6") (pinfunction "V-_6") (pintype "passive"))
      (node (ref "U35") (pin "6") (pinfunction "V-_6") (pintype "passive"))
      (node (ref "U36") (pin "6") (pinfunction "V-_6") (pintype "passive"))
      (node (ref "U37") (pin "6") (pinfunction "V-_6") (pintype "passive"))
      (node (ref "U38") (pin "6") (pinfunction "V-_6") (pintype "passive"))
      (node (ref "U40") (pin "6") (pinfunction "V-_6") (pintype "passive"))
      (node (ref "U41") (pin "6") (pinfunction "V-_6") (pintype "passive"))
      (node (ref "U42") (pin "6") (pinfunction "V-_6") (pintype "passive"))
    )
    (net (code "3") (name "/1V5_IL") (class "Default")
      (node (ref "R107") (pin "1") (pinfunction "A_1") (pintype "passive"))
      (node (ref "R123") (pin "1") (pinfunction "A_1") (pintype "passive"))
      (node (ref "R139") (pin "1") (pinfunction "A_1") (pintype "passive"))
      (node (ref "U32") (pin "2") (pinfunction "1V5_2") (pintype "passive"))
    )
    (net (code "4") (name "/1V5_Io") (class "Default")
      (node (ref "R153") (pin "1") (pinfunction "A_1") (pintype "passive"))
      (node (ref "R161") (pin "1") (pinfunction "A_1") (pintype "passive"))
      (node (ref "R169") (pin "1") (pinfunction "A_1") (pintype "passive"))
      (node (ref "U39") (pin "2") (pinfunction "1V5_2") (pintype "passive"))
    )
    (net (code "5") (name "/1V5_Vo") (class "Default")
      (node (ref "R106") (pin "1") (pinfunction "A_1") (pintype "passive"))
      (node (ref "R122") (pin "1") (pinfunction "A_1") (pintype "passive"))
      (node (ref "R138") (pin "1") (pinfunction "A_1") (pintype "passive"))
      (node (ref "U31") (pin "2") (pinfunction "1V5_2") (pintype "passive"))
    )
    (net (code "6") (name "/OUT1+") (class "Default")
      (node (ref "C223") (pin "1") (pinfunction "OUT_1") (pintype "passive"))
      (node (ref "R113") (pin "2") (pinfunction "A_2") (pintype "passive"))
      (node (ref "R119") (pin "1") (pinfunction "A_1") (pintype "passive"))
      (node (ref "U34") (pin "4") (pinfunction "OUT+_4") (pintype "passive"))
    )
    (net (code "7") (name "/OUT1-") (class "Default")
      (node (ref "C211") (pin "1") (pinfunction "OUT_1") (pintype "passive"))
      (node (ref "R105") (pin "1") (pinfunction "A_1") (pintype "passive"))
      (node (ref "R113") (pin "1") (pinfunction "A_1") (pintype "passive"))
      (node (ref "U34") (pin "5") (pinfunction "OUT-_5") (pintype "passive"))
    )
    (net (code "8") (name "/OUT2+") (class "Default")
      (node (ref "C237") (pin "1") (pinfunction "OUT_1") (pintype "passive"))
      (node (ref "R129") (pin "2") (pinfunction "A_2") (pintype "passive"))
      (node (ref "R135") (pin "1") (pinfunction "A_1") (pintype "passive"))
      (node (ref "U36") (pin "4") (pinfunction "OUT+_4") (pintype "passive"))
    )
    (net (code "9") (name "/OUT2-") (class "Default")
      (node (ref "C225") (pin "1") (pinfunction "OUT_1") (pintype "passive"))
      (node (ref "R121") (pin "1") (pinfunction "A_1") (pintype "passive"))
      (node (ref "R129") (pin "1") (pinfunction "A_1") (pintype "passive"))
      (node (ref "U36") (pin "5") (pinfunction "OUT-_5") (pintype "passive"))
    )
    (net (code "10") (name "/OUT3+") (class "Default")
      (node (ref "C251") (pin "1") (pinfunction "OUT_1") (pintype "passive"))
      (node (ref "R145") (pin "2") (pinfunction "A_2") (pintype "passive"))
      (node (ref "R151") (pin "1") (pinfunction "A_1") (pintype "passive"))
      (node (ref "U38") (pin "4") (pinfunction "OUT+_4") (pintype "passive"))
    )
    (net (code "11") (name "/OUT3-") (class "Default")
      (node (ref "C239") (pin "1") (pinfunction "OUT_1") (pintype "passive"))
      (node (ref "R137") (pin "1") (pinfunction "A_1") (pintype "passive"))
      (node (ref "R145") (pin "1") (pinfunction "A_1") (pintype "passive"))
      (node (ref "U38") (pin "5") (pinfunction "OUT-_5") (pintype "passive"))
    )
    (net (code "12") (name "/OUT4+") (class "Default")
      (node (ref "C222") (pin "1") (pinfunction "OUT_1") (pintype "passive"))
      (node (ref "R112") (pin "2") (pinfunction "A_2") (pintype "passive"))
      (node (ref "R117") (pin "1") (pinfunction "A_1") (pintype "passive"))
      (node (ref "U33") (pin "4") (pinfunction "OUT+_4") (pintype "passive"))
    )
    (net (code "13") (name "/OUT4-") (class "Default")
      (node (ref "C210") (pin "1") (pinfunction "OUT_1") (pintype "passive"))
      (node (ref "R104") (pin "1") (pinfunction "A_1") (pintype "passive"))
      (node (ref "R112") (pin "1") (pinfunction "A_1") (pintype "passive"))
      (node (ref "U33") (pin "5") (pinfunction "OUT-_5") (pintype "passive"))
    )
    (net (code "14") (name "/OUT5+") (class "Default")
      (node (ref "C236") (pin "1") (pinfunction "OUT_1") (pintype "passive"))
      (node (ref "R128") (pin "2") (pinfunction "A_2") (pintype "passive"))
      (node (ref "R133") (pin "1") (pinfunction "A_1") (pintype "passive"))
      (node (ref "U35") (pin "4") (pinfunction "OUT+_4") (pintype "passive"))
    )
    (net (code "15") (name "/OUT5-") (class "Default")
      (node (ref "C224") (pin "1") (pinfunction "OUT_1") (pintype "passive"))
      (node (ref "R120") (pin "1") (pinfunction "A_1") (pintype "passive"))
      (node (ref "R128") (pin "1") (pinfunction "A_1") (pintype "passive"))
      (node (ref "U35") (pin "5") (pinfunction "OUT-_5") (pintype "passive"))
    )
    (net (code "16") (name "/OUT6+") (class "Default")
      (node (ref "C250") (pin "1") (pinfunction "OUT_1") (pintype "passive"))
      (node (ref "R144") (pin "2") (pinfunction "A_2") (pintype "passive"))
      (node (ref "R149") (pin "1") (pinfunction "A_1") (pintype "passive"))
      (node (ref "U37") (pin "4") (pinfunction "OUT+_4") (pintype "passive"))
    )
    (net (code "17") (name "/OUT6-") (class "Default")
      (node (ref "C238") (pin "1") (pinfunction "OUT_1") (pintype "passive"))
      (node (ref "R136") (pin "1") (pinfunction "A_1") (pintype "passive"))
      (node (ref "R144") (pin "1") (pinfunction "A_1") (pintype "passive"))
      (node (ref "U37") (pin "5") (pinfunction "OUT-_5") (pintype "passive"))
    )
    (net (code "18") (name "/OUT7+") (class "Default")
      (node (ref "C260") (pin "1") (pinfunction "OUT_1") (pintype "passive"))
      (node (ref "R156") (pin "2") (pinfunction "A_2") (pintype "passive"))
      (node (ref "R159") (pin "1") (pinfunction "A_1") (pintype "passive"))
      (node (ref "U40") (pin "4") (pinfunction "OUT+_4") (pintype "passive"))
    )
    (net (code "19") (name "/OUT7-") (class "Default")
      (node (ref "C254") (pin "1") (pinfunction "OUT_1") (pintype "passive"))
      (node (ref "R152") (pin "1") (pinfunction "A_1") (pintype "passive"))
      (node (ref "R156") (pin "1") (pinfunction "A_1") (pintype "passive"))
      (node (ref "U40") (pin "5") (pinfunction "OUT-_5") (pintype "passive"))
    )
    (net (code "20") (name "/OUT8+") (class "Default")
      (node (ref "C267") (pin "1") (pinfunction "OUT_1") (pintype "passive"))
      (node (ref "R164") (pin "2") (pinfunction "A_2") (pintype "passive"))
      (node (ref "R167") (pin "1") (pinfunction "A_1") (pintype "passive"))
      (node (ref "U41") (pin "4") (pinfunction "OUT+_4") (pintype "passive"))
    )
    (net (code "21") (name "/OUT8-") (class "Default")
      (node (ref "C261") (pin "1") (pinfunction "OUT_1") (pintype "passive"))
      (node (ref "R160") (pin "1") (pinfunction "A_1") (pintype "passive"))
      (node (ref "R164") (pin "1") (pinfunction "A_1") (pintype "passive"))
      (node (ref "U41") (pin "5") (pinfunction "OUT-_5") (pintype "passive"))
    )
    (net (code "22") (name "/OUT9+") (class "Default")
      (node (ref "C274") (pin "1") (pinfunction "OUT_1") (pintype "passive"))
      (node (ref "R172") (pin "2") (pinfunction "A_2") (pintype "passive"))
      (node (ref "R175") (pin "1") (pinfunction "A_1") (pintype "passive"))
      (node (ref "U42") (pin "4") (pinfunction "OUT+_4") (pintype "passive"))
    )
    (net (code "23") (name "/OUT9-") (class "Default")
      (node (ref "C268") (pin "1") (pinfunction "OUT_1") (pintype "passive"))
      (node (ref "R168") (pin "1") (pinfunction "A_1") (pintype "passive"))
      (node (ref "R172") (pin "1") (pinfunction "A_1") (pintype "passive"))
      (node (ref "U42") (pin "5") (pinfunction "OUT-_5") (pintype "passive"))
    )
    (net (code "24") (name "/OUT_IUN1") (class "Default")
      (node (ref "R115") (pin "2") (pinfunction "A_2") (pintype "passive"))
      (node (ref "R118") (pin "1") (pinfunction "A_1") (pintype "passive"))
    )
    (net (code "25") (name "/OUT_IUN2") (class "Default")
      (node (ref "R157") (pin "2") (pinfunction "A_2") (pintype "passive"))
      (node (ref "R158") (pin "1") (pinfunction "A_1") (pintype "passive"))
    )
    (net (code "26") (name "/OUT_IUP1") (class "Default")
      (node (ref "R109") (pin "2") (pinfunction "A_2") (pintype "passive"))
      (node (ref "R111") (pin "1") (pinfunction "A_1") (pintype "passive"))
    )
    (net (code "27") (name "/OUT_IUP2") (class "Default")
      (node (ref "R154") (pin "2") (pinfunction "A_2") (pintype "passive"))
      (node (ref "R155") (pin "1") (pinfunction "A_1") (pintype "passive"))
    )
    (net (code "28") (name "/OUT_IVN1") (class "Default")
      (node (ref "R131") (pin "2") (pinfunction "A_2") (pintype "passive"))
      (node (ref "R134") (pin "1") (pinfunction "A_1") (pintype "passive"))
    )
    (net (code "29") (name "/OUT_IVN2") (class "Default")
      (node (ref "R165") (pin "2") (pinfunction "A_2") (pintype "passive"))
      (node (ref "R166") (pin "1") (pinfunction "A_1") (pintype "passive"))
    )
    (net (code "30") (name "/OUT_IVP1") (class "Default")
      (node (ref "R125") (pin "2") (pinfunction "A_2") (pintype "passive"))
      (node (ref "R127") (pin "1") (pinfunction "A_1") (pintype "passive"))
    )
    (net (code "31") (name "/OUT_IVP2") (class "Default")
      (node (ref "R162") (pin "2") (pinfunction "A_2") (pintype "passive"))
      (node (ref "R163") (pin "1") (pinfunction "A_1") (pintype "passive"))
    )
    (net (code "32") (name "/OUT_IWN1") (class "Default")
      (node (ref "R147") (pin "2") (pinfunction "A_2") (pintype "passive"))
      (node (ref "R150") (pin "1") (pinfunction "A_1") (pintype "passive"))
    )
    (net (code "33") (name "/OUT_IWN2") (class "Default")
      (node (ref "R173") (pin "2") (pinfunction "A_2") (pintype "passive"))
      (node (ref "R174") (pin "1") (pinfunction "A_1") (pintype "passive"))
    )
    (net (code "34") (name "/OUT_IWP1") (class "Default")
      (node (ref "R141") (pin "2") (pinfunction "A_2") (pintype "passive"))
      (node (ref "R143") (pin "1") (pinfunction "A_1") (pintype "passive"))
    )
    (net (code "35") (name "/OUT_IWP2") (class "Default")
      (node (ref "R170") (pin "2") (pinfunction "A_2") (pintype "passive"))
      (node (ref "R171") (pin "1") (pinfunction "A_1") (pintype "passive"))
    )
    (net (code "36") (name "/OUT_VUN") (class "Default")
      (node (ref "R114") (pin "2") (pinfunction "A_2") (pintype "passive"))
      (node (ref "R116") (pin "1") (pinfunction "A_1") (pintype "passive"))
    )
    (net (code "37") (name "/OUT_VUP") (class "Default")
      (node (ref "R108") (pin "2") (pinfunction "A_2") (pintype "passive"))
      (node (ref "R110") (pin "1") (pinfunction "A_1") (pintype "passive"))
    )
    (net (code "38") (name "/OUT_VVN") (class "Default")
      (node (ref "R130") (pin "2") (pinfunction "A_2") (pintype "passive"))
      (node (ref "R132") (pin "1") (pinfunction "A_1") (pintype "passive"))
    )
    (net (code "39") (name "/OUT_VVP") (class "Default")
      (node (ref "R124") (pin "2") (pinfunction "A_2") (pintype "passive"))
      (node (ref "R126") (pin "1") (pinfunction "A_1") (pintype "passive"))
    )
    (net (code "40") (name "/OUT_VWN") (class "Default")
      (node (ref "R146") (pin "2") (pinfunction "A_2") (pintype "passive"))
      (node (ref "R148") (pin "1") (pinfunction "A_1") (pintype "passive"))
    )
    (net (code "41") (name "/OUT_VWP") (class "Default")
      (node (ref "R140") (pin "2") (pinfunction "A_2") (pintype "passive"))
      (node (ref "R142") (pin "1") (pinfunction "A_1") (pintype "passive"))
    )
    (net (code "42") (name "/Vocm_IL1") (class "Default")
      (node (ref "C213") (pin "2") (pinfunction "OUT_2") (pintype "passive"))
      (node (ref "R107") (pin "2") (pinfunction "A_2") (pintype "passive"))
      (node (ref "U34") (pin "2") (pinfunction "Vocm_2") (pintype "power_in"))
    )
    (net (code "43") (name "/Vocm_IL2") (class "Default")
      (node (ref "C227") (pin "2") (pinfunction "OUT_2") (pintype "passive"))
      (node (ref "R123") (pin "2") (pinfunction "A_2") (pintype "passive"))
      (node (ref "U36") (pin "2") (pinfunction "Vocm_2") (pintype "power_in"))
    )
    (net (code "44") (name "/Vocm_IL3") (class "Default")
      (node (ref "C241") (pin "2") (pinfunction "OUT_2") (pintype "passive"))
      (node (ref "R139") (pin "2") (pinfunction "A_2") (pintype "passive"))
      (node (ref "U38") (pin "2") (pinfunction "Vocm_2") (pintype "power_in"))
    )
    (net (code "45") (name "/Vocm_Io1") (class "Default")
      (node (ref "C255") (pin "2") (pinfunction "OUT_2") (pintype "passive"))
      (node (ref "R153") (pin "2") (pinfunction "A_2") (pintype "passive"))
      (node (ref "U40") (pin "2") (pinfunction "Vocm_2") (pintype "power_in"))
    )
    (net (code "46") (name "/Vocm_Io2") (class "Default")
      (node (ref "C262") (pin "2") (pinfunction "OUT_2") (pintype "passive"))
      (node (ref "R161") (pin "2") (pinfunction "A_2") (pintype "passive"))
      (node (ref "U41") (pin "2") (pinfunction "Vocm_2") (pintype "power_in"))
    )
    (net (code "47") (name "/Vocm_Io3") (class "Default")
      (node (ref "C269") (pin "2") (pinfunction "OUT_2") (pintype "passive"))
      (node (ref "R169") (pin "2") (pinfunction "A_2") (pintype "passive"))
      (node (ref "U42") (pin "2") (pinfunction "Vocm_2") (pintype "power_in"))
    )
    (net (code "48") (name "/Vocm_Vo1") (class "Default")
      (node (ref "C212") (pin "2") (pinfunction "OUT_2") (pintype "passive"))
      (node (ref "R106") (pin "2") (pinfunction "A_2") (pintype "passive"))
      (node (ref "U33") (pin "2") (pinfunction "Vocm_2") (pintype "power_in"))
    )
    (net (code "49") (name "/Vocm_Vo2") (class "Default")
      (node (ref "C226") (pin "2") (pinfunction "OUT_2") (pintype "passive"))
      (node (ref "R122") (pin "2") (pinfunction "A_2") (pintype "passive"))
      (node (ref "U35") (pin "2") (pinfunction "Vocm_2") (pintype "power_in"))
    )
    (net (code "50") (name "/Vocm_Vo3") (class "Default")
      (node (ref "C240") (pin "2") (pinfunction "OUT_2") (pintype "passive"))
      (node (ref "R138") (pin "2") (pinfunction "A_2") (pintype "passive"))
      (node (ref "U37") (pin "2") (pinfunction "Vocm_2") (pintype "power_in"))
    )
    (net (code "51") (name "GND_LV") (class "Default")
      (node (ref "C206") (pin "1") (pinfunction "OUT_1") (pintype "passive"))
      (node (ref "C207") (pin "1") (pinfunction "OUT_1") (pintype "passive"))
      (node (ref "C208") (pin "1") (pinfunction "OUT_1") (pintype "passive"))
      (node (ref "C209") (pin "1") (pinfunction "OUT_1") (pintype "passive"))
      (node (ref "C212") (pin "1") (pinfunction "OUT_1") (pintype "passive"))
      (node (ref "C213") (pin "1") (pinfunction "OUT_1") (pintype "passive"))
      (node (ref "C214") (pin "1") (pinfunction "OUT_1") (pintype "passive"))
      (node (ref "C215") (pin "1") (pinfunction "OUT_1") (pintype "passive"))
      (node (ref "C216") (pin "1") (pinfunction "OUT_1") (pintype "passive"))
      (node (ref "C217") (pin "1") (pinfunction "OUT_1") (pintype "passive"))
      (node (ref "C218") (pin "2") (pinfunction "OUT_2") (pintype "passive"))
      (node (ref "C219") (pin "2") (pinfunction "OUT_2") (pintype "passive"))
      (node (ref "C220") (pin "2") (pinfunction "OUT_2") (pintype "passive"))
      (node (ref "C221") (pin "2") (pinfunction "OUT_2") (pintype "passive"))
      (node (ref "C226") (pin "1") (pinfunction "OUT_1") (pintype "passive"))
      (node (ref "C227") (pin "1") (pinfunction "OUT_1") (pintype "passive"))
      (node (ref "C228") (pin "1") (pinfunction "OUT_1") (pintype "passive"))
      (node (ref "C229") (pin "1") (pinfunction "OUT_1") (pintype "passive"))
      (node (ref "C230") (pin "1") (pinfunction "OUT_1") (pintype "passive"))
      (node (ref "C231") (pin "1") (pinfunction "OUT_1") (pintype "passive"))
      (node (ref "C232") (pin "2") (pinfunction "OUT_2") (pintype "passive"))
      (node (ref "C233") (pin "2") (pinfunction "OUT_2") (pintype "passive"))
      (node (ref "C234") (pin "2") (pinfunction "OUT_2") (pintype "passive"))
      (node (ref "C235") (pin "2") (pinfunction "OUT_2") (pintype "passive"))
      (node (ref "C240") (pin "1") (pinfunction "OUT_1") (pintype "passive"))
      (node (ref "C241") (pin "1") (pinfunction "OUT_1") (pintype "passive"))
      (node (ref "C242") (pin "1") (pinfunction "OUT_1") (pintype "passive"))
      (node (ref "C243") (pin "1") (pinfunction "OUT_1") (pintype "passive"))
      (node (ref "C244") (pin "1") (pinfunction "OUT_1") (pintype "passive"))
      (node (ref "C245") (pin "1") (pinfunction "OUT_1") (pintype "passive"))
      (node (ref "C246") (pin "2") (pinfunction "OUT_2") (pintype "passive"))
      (node (ref "C247") (pin "2") (pinfunction "OUT_2") (pintype "passive"))
      (node (ref "C248") (pin "2") (pinfunction "OUT_2") (pintype "passive"))
      (node (ref "C249") (pin "2") (pinfunction "OUT_2") (pintype "passive"))
      (node (ref "C252") (pin "1") (pinfunction "OUT_1") (pintype "passive"))
      (node (ref "C253") (pin "1") (pinfunction "OUT_1") (pintype "passive"))
      (node (ref "C255") (pin "1") (pinfunction "OUT_1") (pintype "passive"))
      (node (ref "C256") (pin "1") (pinfunction "OUT_1") (pintype "passive"))
      (node (ref "C257") (pin "1") (pinfunction "OUT_1") (pintype "passive"))
      (node (ref "C258") (pin "2") (pinfunction "OUT_2") (pintype "passive"))
      (node (ref "C259") (pin "2") (pinfunction "OUT_2") (pintype "passive"))
      (node (ref "C262") (pin "1") (pinfunction "OUT_1") (pintype "passive"))
      (node (ref "C263") (pin "1") (pinfunction "OUT_1") (pintype "passive"))
      (node (ref "C264") (pin "1") (pinfunction "OUT_1") (pintype "passive"))
      (node (ref "C265") (pin "2") (pinfunction "OUT_2") (pintype "passive"))
      (node (ref "C266") (pin "2") (pinfunction "OUT_2") (pintype "passive"))
      (node (ref "C269") (pin "1") (pinfunction "OUT_1") (pintype "passive"))
      (node (ref "C270") (pin "1") (pinfunction "OUT_1") (pintype "passive"))
      (node (ref "C271") (pin "1") (pinfunction "OUT_1") (pintype "passive"))
      (node (ref "C272") (pin "2") (pinfunction "OUT_2") (pintype "passive"))
      (node (ref "C273") (pin "2") (pinfunction "OUT_2") (pintype "passive"))
      (node (ref "R110") (pin "2") (pinfunction "A_2") (pintype "passive"))
      (node (ref "R111") (pin "2") (pinfunction "A_2") (pintype "passive"))
      (node (ref "R116") (pin "2") (pinfunction "A_2") (pintype "passive"))
      (node (ref "R118") (pin "2") (pinfunction "A_2") (pintype "passive"))
      (node (ref "R126") (pin "2") (pinfunction "A_2") (pintype "passive"))
      (node (ref "R127") (pin "2") (pinfunction "A_2") (pintype "passive"))
      (node (ref "R132") (pin "2") (pinfunction "A_2") (pintype "passive"))
      (node (ref "R134") (pin "2") (pinfunction "A_2") (pintype "passive"))
      (node (ref "R142") (pin "2") (pinfunction "A_2") (pintype "passive"))
      (node (ref "R143") (pin "2") (pinfunction "A_2") (pintype "passive"))
      (node (ref "R148") (pin "2") (pinfunction "A_2") (pintype "passive"))
      (node (ref "R150") (pin "2") (pinfunction "A_2") (pintype "passive"))
      (node (ref "R155") (pin "2") (pinfunction "A_2") (pintype "passive"))
      (node (ref "R158") (pin "2") (pinfunction "A_2") (pintype "passive"))
      (node (ref "R163") (pin "2") (pinfunction "A_2") (pintype "passive"))
      (node (ref "R166") (pin "2") (pinfunction "A_2") (pintype "passive"))
      (node (ref "R171") (pin "2") (pinfunction "A_2") (pintype "passive"))
      (node (ref "R174") (pin "2") (pinfunction "A_2") (pintype "passive"))
      (node (ref "U31") (pin "3") (pinfunction "GND_3") (pintype "passive"))
      (node (ref "U32") (pin "3") (pinfunction "GND_3") (pintype "passive"))
      (node (ref "U39") (pin "3") (pinfunction "GND_3") (pintype "passive"))
    )
    (net (code "52") (name "Net-(U33-IN+)") (class "Default")
      (node (ref "C210") (pin "2") (pinfunction "OUT_2") (pintype "passive"))
      (node (ref "R104") (pin "2") (pinfunction "A_2") (pintype "passive"))
      (node (ref "R108") (pin "1") (pinfunction "A_1") (pintype "passive"))
      (node (ref "U33") (pin "8") (pinfunction "IN+_8") (pintype "passive"))
    )
    (net (code "53") (name "Net-(U33-IN-)") (class "Default")
      (node (ref "C222") (pin "2") (pinfunction "OUT_2") (pintype "passive"))
      (node (ref "R114") (pin "1") (pinfunction "A_1") (pintype "passive"))
      (node (ref "R117") (pin "2") (pinfunction "A_2") (pintype "passive"))
      (node (ref "U33") (pin "1") (pinfunction "IN-_1") (pintype "passive"))
    )
    (net (code "54") (name "Net-(U34-IN+)") (class "Default")
      (node (ref "C211") (pin "2") (pinfunction "OUT_2") (pintype "passive"))
      (node (ref "R105") (pin "2") (pinfunction "A_2") (pintype "passive"))
      (node (ref "R109") (pin "1") (pinfunction "A_1") (pintype "passive"))
      (node (ref "U34") (pin "8") (pinfunction "IN+_8") (pintype "passive"))
    )
    (net (code "55") (name "Net-(U34-IN-)") (class "Default")
      (node (ref "C223") (pin "2") (pinfunction "OUT_2") (pintype "passive"))
      (node (ref "R115") (pin "1") (pinfunction "A_1") (pintype "passive"))
      (node (ref "R119") (pin "2") (pinfunction "A_2") (pintype "passive"))
      (node (ref "U34") (pin "1") (pinfunction "IN-_1") (pintype "passive"))
    )
    (net (code "56") (name "Net-(U35-IN+)") (class "Default")
      (node (ref "C224") (pin "2") (pinfunction "OUT_2") (pintype "passive"))
      (node (ref "R120") (pin "2") (pinfunction "A_2") (pintype "passive"))
      (node (ref "R124") (pin "1") (pinfunction "A_1") (pintype "passive"))
      (node (ref "U35") (pin "8") (pinfunction "IN+_8") (pintype "passive"))
    )
    (net (code "57") (name "Net-(U35-IN-)") (class "Default")
      (node (ref "C236") (pin "2") (pinfunction "OUT_2") (pintype "passive"))
      (node (ref "R130") (pin "1") (pinfunction "A_1") (pintype "passive"))
      (node (ref "R133") (pin "2") (pinfunction "A_2") (pintype "passive"))
      (node (ref "U35") (pin "1") (pinfunction "IN-_1") (pintype "passive"))
    )
    (net (code "58") (name "Net-(U36-IN+)") (class "Default")
      (node (ref "C225") (pin "2") (pinfunction "OUT_2") (pintype "passive"))
      (node (ref "R121") (pin "2") (pinfunction "A_2") (pintype "passive"))
      (node (ref "R125") (pin "1") (pinfunction "A_1") (pintype "passive"))
      (node (ref "U36") (pin "8") (pinfunction "IN+_8") (pintype "passive"))
    )
    (net (code "59") (name "Net-(U36-IN-)") (class "Default")
      (node (ref "C237") (pin "2") (pinfunction "OUT_2") (pintype "passive"))
      (node (ref "R131") (pin "1") (pinfunction "A_1") (pintype "passive"))
      (node (ref "R135") (pin "2") (pinfunction "A_2") (pintype "passive"))
      (node (ref "U36") (pin "1") (pinfunction "IN-_1") (pintype "passive"))
    )
    (net (code "60") (name "Net-(U37-IN+)") (class "Default")
      (node (ref "C238") (pin "2") (pinfunction "OUT_2") (pintype "passive"))
      (node (ref "R136") (pin "2") (pinfunction "A_2") (pintype "passive"))
      (node (ref "R140") (pin "1") (pinfunction "A_1") (pintype "passive"))
      (node (ref "U37") (pin "8") (pinfunction "IN+_8") (pintype "passive"))
    )
    (net (code "61") (name "Net-(U37-IN-)") (class "Default")
      (node (ref "C250") (pin "2") (pinfunction "OUT_2") (pintype "passive"))
      (node (ref "R146") (pin "1") (pinfunction "A_1") (pintype "passive"))
      (node (ref "R149") (pin "2") (pinfunction "A_2") (pintype "passive"))
      (node (ref "U37") (pin "1") (pinfunction "IN-_1") (pintype "passive"))
    )
    (net (code "62") (name "Net-(U38-IN+)") (class "Default")
      (node (ref "C239") (pin "2") (pinfunction "OUT_2") (pintype "passive"))
      (node (ref "R137") (pin "2") (pinfunction "A_2") (pintype "passive"))
      (node (ref "R141") (pin "1") (pinfunction "A_1") (pintype "passive"))
      (node (ref "U38") (pin "8") (pinfunction "IN+_8") (pintype "passive"))
    )
    (net (code "63") (name "Net-(U38-IN-)") (class "Default")
      (node (ref "C251") (pin "2") (pinfunction "OUT_2") (pintype "passive"))
      (node (ref "R147") (pin "1") (pinfunction "A_1") (pintype "passive"))
      (node (ref "R151") (pin "2") (pinfunction "A_2") (pintype "passive"))
      (node (ref "U38") (pin "1") (pinfunction "IN-_1") (pintype "passive"))
    )
    (net (code "64") (name "Net-(U40-IN+)") (class "Default")
      (node (ref "C254") (pin "2") (pinfunction "OUT_2") (pintype "passive"))
      (node (ref "R152") (pin "2") (pinfunction "A_2") (pintype "passive"))
      (node (ref "R154") (pin "1") (pinfunction "A_1") (pintype "passive"))
      (node (ref "U40") (pin "8") (pinfunction "IN+_8") (pintype "passive"))
    )
    (net (code "65") (name "Net-(U40-IN-)") (class "Default")
      (node (ref "C260") (pin "2") (pinfunction "OUT_2") (pintype "passive"))
      (node (ref "R157") (pin "1") (pinfunction "A_1") (pintype "passive"))
      (node (ref "R159") (pin "2") (pinfunction "A_2") (pintype "passive"))
      (node (ref "U40") (pin "1") (pinfunction "IN-_1") (pintype "passive"))
    )
    (net (code "66") (name "Net-(U41-IN+)") (class "Default")
      (node (ref "C261") (pin "2") (pinfunction "OUT_2") (pintype "passive"))
      (node (ref "R160") (pin "2") (pinfunction "A_2") (pintype "passive"))
      (node (ref "R162") (pin "1") (pinfunction "A_1") (pintype "passive"))
      (node (ref "U41") (pin "8") (pinfunction "IN+_8") (pintype "passive"))
    )
    (net (code "67") (name "Net-(U41-IN-)") (class "Default")
      (node (ref "C267") (pin "2") (pinfunction "OUT_2") (pintype "passive"))
      (node (ref "R165") (pin "1") (pinfunction "A_1") (pintype "passive"))
      (node (ref "R167") (pin "2") (pinfunction "A_2") (pintype "passive"))
      (node (ref "U41") (pin "1") (pinfunction "IN-_1") (pintype "passive"))
    )
    (net (code "68") (name "Net-(U42-IN+)") (class "Default")
      (node (ref "C268") (pin "2") (pinfunction "OUT_2") (pintype "passive"))
      (node (ref "R168") (pin "2") (pinfunction "A_2") (pintype "passive"))
      (node (ref "R170") (pin "1") (pinfunction "A_1") (pintype "passive"))
      (node (ref "U42") (pin "8") (pinfunction "IN+_8") (pintype "passive"))
    )
    (net (code "69") (name "Net-(U42-IN-)") (class "Default")
      (node (ref "C274") (pin "2") (pinfunction "OUT_2") (pintype "passive"))
      (node (ref "R173") (pin "1") (pinfunction "A_1") (pintype "passive"))
      (node (ref "R175") (pin "2") (pinfunction "A_2") (pintype "passive"))
      (node (ref "U42") (pin "1") (pinfunction "IN-_1") (pintype "passive"))
    )
    (net (code "70") (name "unconnected-(U33-NC-Pad7)") (class "Default")
      (node (ref "U33") (pin "7") (pinfunction "NC_7") (pintype "power_in"))
    )
    (net (code "71") (name "unconnected-(U34-NC-Pad7)") (class "Default")
      (node (ref "U34") (pin "7") (pinfunction "NC_7") (pintype "power_in"))
    )
    (net (code "72") (name "unconnected-(U35-NC-Pad7)") (class "Default")
      (node (ref "U35") (pin "7") (pinfunction "NC_7") (pintype "power_in"))
    )
    (net (code "73") (name "unconnected-(U36-NC-Pad7)") (class "Default")
      (node (ref "U36") (pin "7") (pinfunction "NC_7") (pintype "power_in"))
    )
    (net (code "74") (name "unconnected-(U37-NC-Pad7)") (class "Default")
      (node (ref "U37") (pin "7") (pinfunction "NC_7") (pintype "power_in"))
    )
    (net (code "75") (name "unconnected-(U38-NC-Pad7)") (class "Default")
      (node (ref "U38") (pin "7") (pinfunction "NC_7") (pintype "power_in"))
    )
    (net (code "76") (name "unconnected-(U40-NC-Pad7)") (class "Default")
      (node (ref "U40") (pin "7") (pinfunction "NC_7") (pintype "power_in"))
    )
    (net (code "77") (name "unconnected-(U41-NC-Pad7)") (class "Default")
      (node (ref "U41") (pin "7") (pinfunction "NC_7") (pintype "power_in"))
    )
    (net (code "78") (name "unconnected-(U42-NC-Pad7)") (class "Default")
      (node (ref "U42") (pin "7") (pinfunction "NC_7") (pintype "power_in"))
    )
  )
)
